# comp-btm.net
KiCad netlist of a schematic drawn in EAGLE
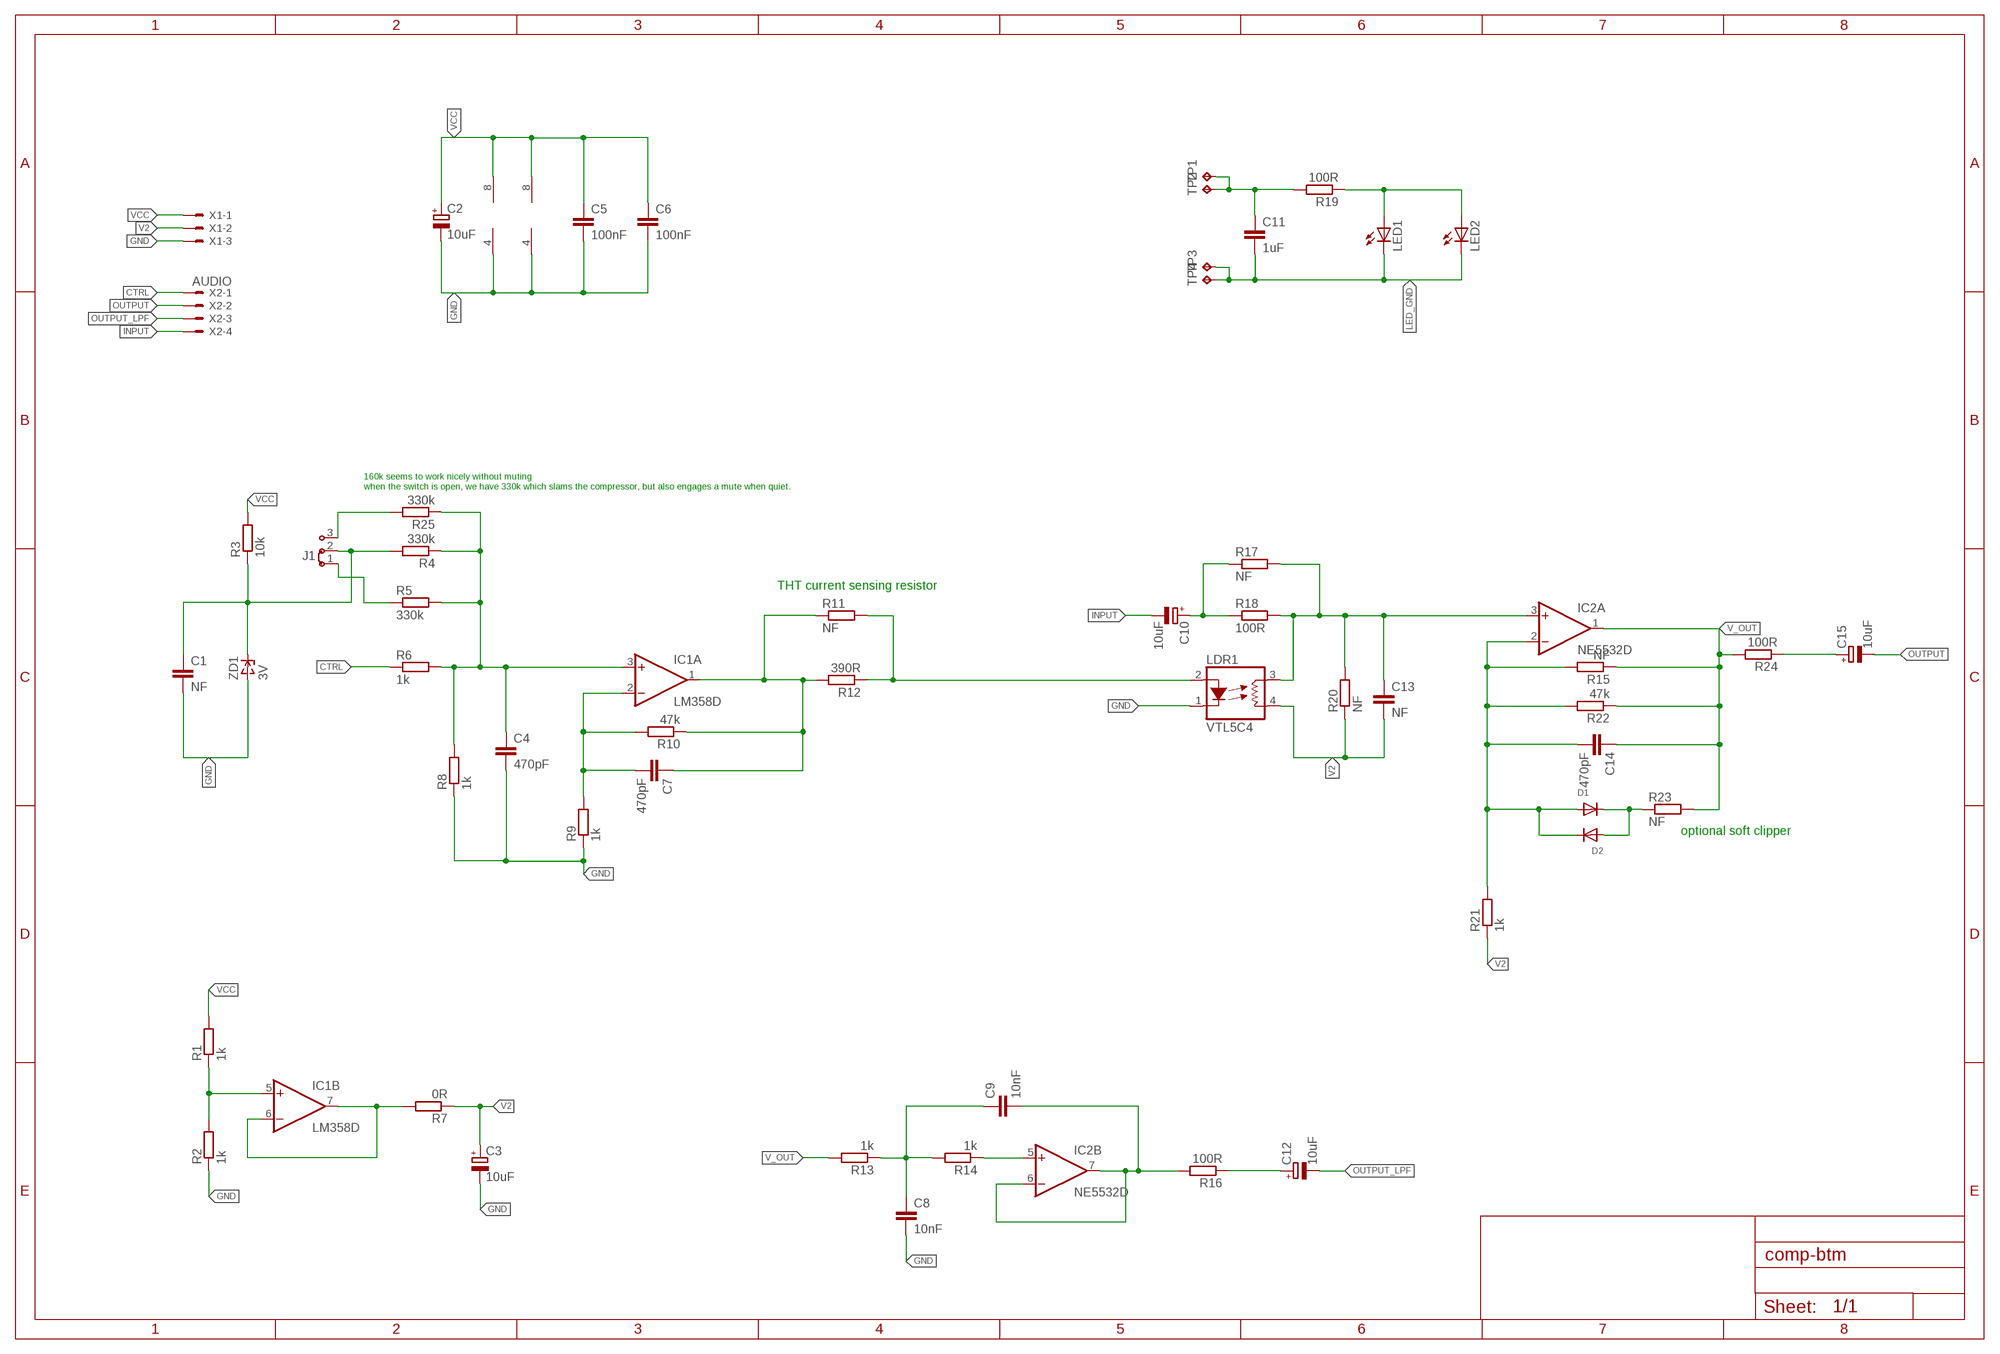
[diagram p0: schematic, sheet 1]

(export (version "E")
  (design (tool "Eeschema 10.0.6"))
  (components
    (comp (ref "C1")
      (value "NF")
      (footprint "eagle-import:C0805")
      (libsource (lib "eagle-import") (part "C-EUC0805"))
    )
    (comp (ref "C2")
      (value "10uF")
      (footprint "eagle-import:E2,5-6E")
      (libsource (lib "eagle-import") (part "CPOL-EUE2,5-6E"))
    )
    (comp (ref "C3")
      (value "10uF")
      (footprint "eagle-import:E2,5-6E")
      (libsource (lib "eagle-import") (part "CPOL-EUE2,5-6E"))
    )
    (comp (ref "C4")
      (value "470pF")
      (footprint "eagle-import:C0805")
      (libsource (lib "eagle-import") (part "C-EUC0805"))
    )
    (comp (ref "C5")
      (value "100nF")
      (footprint "eagle-import:C0805")
      (libsource (lib "eagle-import") (part "C-EUC0805"))
    )
    (comp (ref "C6")
      (value "100nF")
      (footprint "eagle-import:C0805")
      (libsource (lib "eagle-import") (part "C-EUC0805"))
    )
    (comp (ref "C7")
      (value "470pF")
      (footprint "eagle-import:C0805")
      (libsource (lib "eagle-import") (part "C-EUC0805"))
    )
    (comp (ref "C8")
      (value "10nF")
      (footprint "eagle-import:C0805")
      (libsource (lib "eagle-import") (part "C-EUC0805"))
    )
    (comp (ref "C9")
      (value "10nF")
      (footprint "eagle-import:C0805")
      (libsource (lib "eagle-import") (part "C-EUC0805"))
    )
    (comp (ref "C10")
      (value "10uF")
      (footprint "eagle-import:E2,5-6E")
      (libsource (lib "eagle-import") (part "CPOL-EUE2,5-6E"))
    )
    (comp (ref "C11")
      (value "1uF")
      (footprint "eagle-import:C0805")
      (libsource (lib "eagle-import") (part "C-EUC0805"))
    )
    (comp (ref "C12")
      (value "10uF")
      (footprint "eagle-import:E2,5-6E")
      (libsource (lib "eagle-import") (part "CPOL-EUE2,5-6E"))
    )
    (comp (ref "C13")
      (value "NF")
      (footprint "eagle-import:C0805")
      (libsource (lib "eagle-import") (part "C-EUC0805"))
    )
    (comp (ref "C14")
      (value "470pF")
      (footprint "eagle-import:C0805")
      (libsource (lib "eagle-import") (part "C-EUC0805"))
    )
    (comp (ref "C15")
      (value "10uF")
      (footprint "eagle-import:E2,5-6E")
      (libsource (lib "eagle-import") (part "CPOL-EUE2,5-6E"))
    )
    (comp (ref "D1")
      (value "DIODEDO-1N4148")
      (footprint "eagle-import:DO-1N4148")
      (libsource (lib "eagle-import") (part "DIODEDO-1N4148"))
    )
    (comp (ref "D2")
      (value "DIODEDO-1N4148")
      (footprint "eagle-import:DO-1N4148")
      (libsource (lib "eagle-import") (part "DIODEDO-1N4148"))
    )
    (comp (ref "IC1")
      (value "LM358D")
      (footprint "eagle-import:SO08")
      (libsource (lib "eagle-import") (part "LM358D"))
    )
    (comp (ref "IC2")
      (value "NE5532D")
      (footprint "eagle-import:SO08")
      (libsource (lib "eagle-import") (part "NE5532D"))
    )
    (comp (ref "J1")
      (value "J2X2MM")
      (footprint "eagle-import:04C")
      (libsource (lib "eagle-import") (part "J2X2MM"))
    )
    (comp (ref "LDR1")
      (value "VTL5C4")
      (footprint "eagle-import:VTL5C")
      (fields (field (name "MF") "VACTEC PHOTO") (field (name "MPN") "VTL5C9"))
      (libsource (lib "eagle-import") (part "VTL5C9"))
    )
    (comp (ref "LED1")
      (value "LEDCHIPLED_1206")
      (footprint "eagle-import:CHIPLED_1206")
      (libsource (lib "eagle-import") (part "LEDCHIPLED_1206"))
    )
    (comp (ref "LED2")
      (value "LEDCHIPLED_1206")
      (footprint "eagle-import:CHIPLED_1206")
      (libsource (lib "eagle-import") (part "LEDCHIPLED_1206"))
    )
    (comp (ref "R1")
      (value "1k")
      (footprint "eagle-import:R0805")
      (libsource (lib "eagle-import") (part "R-EU_R0805"))
    )
    (comp (ref "R2")
      (value "1k")
      (footprint "eagle-import:R0805")
      (libsource (lib "eagle-import") (part "R-EU_R0805"))
    )
    (comp (ref "R3")
      (value "10k")
      (footprint "eagle-import:R0805")
      (libsource (lib "eagle-import") (part "R-EU_R0805"))
    )
    (comp (ref "R4")
      (value "330k")
      (footprint "eagle-import:R0805")
      (libsource (lib "eagle-import") (part "R-EU_R0805"))
    )
    (comp (ref "R5")
      (value "330k")
      (footprint "eagle-import:R0805")
      (libsource (lib "eagle-import") (part "R-EU_R0805"))
    )
    (comp (ref "R6")
      (value "1k")
      (footprint "eagle-import:R0805")
      (libsource (lib "eagle-import") (part "R-EU_R0805"))
    )
    (comp (ref "R7")
      (value "0R")
      (footprint "eagle-import:R0805")
      (libsource (lib "eagle-import") (part "R-EU_R0805"))
    )
    (comp (ref "R8")
      (value "1k")
      (footprint "eagle-import:R0805")
      (libsource (lib "eagle-import") (part "R-EU_R0805"))
    )
    (comp (ref "R9")
      (value "1k")
      (footprint "eagle-import:R0805")
      (libsource (lib "eagle-import") (part "R-EU_R0805"))
    )
    (comp (ref "R10")
      (value "47k")
      (footprint "eagle-import:R0805")
      (libsource (lib "eagle-import") (part "R-EU_R0805"))
    )
    (comp (ref "R11")
      (value "NF")
      (footprint "eagle-import:0309V")
      (libsource (lib "eagle-import") (part "R-EU_0309/V"))
    )
    (comp (ref "R12")
      (value "390R")
      (footprint "eagle-import:R0805")
      (libsource (lib "eagle-import") (part "R-EU_R0805"))
    )
    (comp (ref "R13")
      (value "1k")
      (footprint "eagle-import:R0805")
      (libsource (lib "eagle-import") (part "R-EU_R0805"))
    )
    (comp (ref "R14")
      (value "1k")
      (footprint "eagle-import:R0805")
      (libsource (lib "eagle-import") (part "R-EU_R0805"))
    )
    (comp (ref "R15")
      (value "NF")
      (footprint "eagle-import:0309V")
      (libsource (lib "eagle-import") (part "R-EU_0309/V"))
    )
    (comp (ref "R16")
      (value "100R")
      (footprint "eagle-import:R0805")
      (libsource (lib "eagle-import") (part "R-EU_R0805"))
    )
    (comp (ref "R17")
      (value "NF")
      (footprint "eagle-import:0309V")
      (libsource (lib "eagle-import") (part "R-EU_0309/V"))
    )
    (comp (ref "R18")
      (value "100R")
      (footprint "eagle-import:R0805")
      (libsource (lib "eagle-import") (part "R-EU_R0805"))
    )
    (comp (ref "R19")
      (value "100R")
      (footprint "eagle-import:R0805")
      (libsource (lib "eagle-import") (part "R-EU_R0805"))
    )
    (comp (ref "R20")
      (value "NF")
      (footprint "eagle-import:R0805")
      (libsource (lib "eagle-import") (part "R-EU_R0805"))
    )
    (comp (ref "R21")
      (value "1k")
      (footprint "eagle-import:R0805")
      (libsource (lib "eagle-import") (part "R-EU_R0805"))
    )
    (comp (ref "R22")
      (value "47k")
      (footprint "eagle-import:R0805")
      (libsource (lib "eagle-import") (part "R-EU_R0805"))
    )
    (comp (ref "R23")
      (value "NF")
      (footprint "eagle-import:0309V")
      (libsource (lib "eagle-import") (part "R-EU_0309/V"))
    )
    (comp (ref "R24")
      (value "100R")
      (footprint "eagle-import:R0805")
      (libsource (lib "eagle-import") (part "R-EU_R0805"))
    )
    (comp (ref "R25")
      (value "330k")
      (footprint "eagle-import:R0805")
      (libsource (lib "eagle-import") (part "R-EU_R0805"))
    )
    (comp (ref "TP1")
      (value "+")
      (footprint "eagle-import:TP20SQ")
      (libsource (lib "eagle-import") (part "TPTP20SQ"))
    )
    (comp (ref "TP2")
      (value "TPTP20SQ")
      (footprint "eagle-import:TP20SQ")
      (libsource (lib "eagle-import") (part "TPTP20SQ"))
    )
    (comp (ref "TP3")
      (value "TPTP20SQ")
      (footprint "eagle-import:TP20SQ")
      (libsource (lib "eagle-import") (part "TPTP20SQ"))
    )
    (comp (ref "TP4")
      (value "TPTP20SQ")
      (footprint "eagle-import:TP20SQ")
      (libsource (lib "eagle-import") (part "TPTP20SQ"))
    )
    (comp (ref "X1")
      (value "POWER")
      (footprint "eagle-import:JST-XH-03-PACKAGE-LONG-PAD")
      (libsource (lib "eagle-import") (part "JST-XH-03-PIN-LONG-PAD"))
    )
    (comp (ref "X2")
      (value "AUDIO")
      (footprint "eagle-import:JST-XH-04-PACKAGE-LONG-PAD")
      (libsource (lib "eagle-import") (part "JST-XH-04-PIN-LONG-PAD"))
    )
    (comp (ref "ZD1")
      (value "3V")
      (footprint "eagle-import:SOD-123")
      (libsource (lib "eagle-import") (part "ZENERSOD-123"))
    )
  )
  (nets
    (net (code "1") (name "CTRL") (class "Default")
      (node (ref "R6") (pin "1") (pinfunction "1_1") (pintype "passive"))
      (node (ref "X2") (pin "1") (pinfunction "S_1") (pintype "passive"))
    )
    (net (code "2") (name "GND") (class "Default")
      (node (ref "C1") (pin "2") (pinfunction "2_2") (pintype "passive"))
      (node (ref "C2") (pin "-") (pinfunction "-_-") (pintype "passive"))
      (node (ref "C3") (pin "-") (pinfunction "-_-") (pintype "passive"))
      (node (ref "C4") (pin "2") (pinfunction "2_2") (pintype "passive"))
      (node (ref "C5") (pin "2") (pinfunction "2_2") (pintype "passive"))
      (node (ref "C6") (pin "2") (pinfunction "2_2") (pintype "passive"))
      (node (ref "C8") (pin "2") (pinfunction "2_2") (pintype "passive"))
      (node (ref "IC1") (pin "4") (pinfunction "V-_4") (pintype "power_in"))
      (node (ref "IC2") (pin "4") (pinfunction "V-_4") (pintype "power_in"))
      (node (ref "LDR1") (pin "1") (pinfunction "C_1") (pintype "passive"))
      (node (ref "R2") (pin "1") (pinfunction "1_1") (pintype "passive"))
      (node (ref "R8") (pin "1") (pinfunction "1_1") (pintype "passive"))
      (node (ref "R9") (pin "1") (pinfunction "1_1") (pintype "passive"))
      (node (ref "X1") (pin "3") (pinfunction "S_3") (pintype "passive"))
      (node (ref "ZD1") (pin "A") (pinfunction "A_A") (pintype "passive"))
    )
    (net (code "3") (name "INPUT") (class "Default")
      (node (ref "C10") (pin "-") (pinfunction "-_-") (pintype "passive"))
      (node (ref "X2") (pin "4") (pinfunction "S_4") (pintype "passive"))
    )
    (net (code "4") (name "LED_GND") (class "Default")
      (node (ref "C11") (pin "2") (pinfunction "2_2") (pintype "passive"))
      (node (ref "LED1") (pin "C") (pinfunction "C_C") (pintype "passive"))
      (node (ref "LED2") (pin "C") (pinfunction "C_C") (pintype "passive"))
      (node (ref "TP3") (pin "TP") (pinfunction "TP_TP") (pintype "input"))
      (node (ref "TP4") (pin "TP") (pinfunction "TP_TP") (pintype "input"))
    )
    (net (code "5") (name "Net-(C1-Pad1)") (class "Default")
      (node (ref "C1") (pin "1") (pinfunction "1_1") (pintype "passive"))
      (node (ref "J1") (pin "2") (pinfunction "2_2") (pintype "passive"))
      (node (ref "R3") (pin "1") (pinfunction "1_1") (pintype "passive"))
      (node (ref "R4") (pin "2") (pinfunction "2_2") (pintype "passive"))
      (node (ref "ZD1") (pin "C") (pinfunction "C_C") (pintype "passive"))
    )
    (net (code "6") (name "Net-(C8-Pad1)") (class "Default")
      (node (ref "C8") (pin "1") (pinfunction "1_1") (pintype "passive"))
      (node (ref "C9") (pin "1") (pinfunction "1_1") (pintype "passive"))
      (node (ref "R13") (pin "1") (pinfunction "1_1") (pintype "passive"))
      (node (ref "R14") (pin "2") (pinfunction "2_2") (pintype "passive"))
    )
    (net (code "7") (name "Net-(C10-Pad+)") (class "Default")
      (node (ref "C10") (pin "+") (pinfunction "+_+") (pintype "passive"))
      (node (ref "R17") (pin "1") (pinfunction "1_1") (pintype "passive"))
      (node (ref "R18") (pin "1") (pinfunction "1_1") (pintype "passive"))
    )
    (net (code "8") (name "Net-(C11-Pad1)") (class "Default")
      (node (ref "C11") (pin "1") (pinfunction "1_1") (pintype "passive"))
      (node (ref "R19") (pin "2") (pinfunction "2_2") (pintype "passive"))
      (node (ref "TP1") (pin "TP") (pinfunction "TP_TP") (pintype "input"))
      (node (ref "TP2") (pin "TP") (pinfunction "TP_TP") (pintype "input"))
    )
    (net (code "9") (name "Net-(C12-Pad+)") (class "Default")
      (node (ref "C12") (pin "+") (pinfunction "+_+") (pintype "passive"))
      (node (ref "R16") (pin "1") (pinfunction "1_1") (pintype "passive"))
    )
    (net (code "10") (name "Net-(C15-Pad+)") (class "Default")
      (node (ref "C15") (pin "+") (pinfunction "+_+") (pintype "passive"))
      (node (ref "R24") (pin "1") (pinfunction "1_1") (pintype "passive"))
    )
    (net (code "11") (name "Net-(D1-PadC)") (class "Default")
      (node (ref "D1") (pin "C") (pinfunction "C_C") (pintype "passive"))
      (node (ref "D2") (pin "A") (pinfunction "A_A") (pintype "passive"))
      (node (ref "R23") (pin "1") (pinfunction "1_1") (pintype "passive"))
    )
    (net (code "12") (name "Net-(IC1A-+IN)") (class "Default")
      (node (ref "C4") (pin "1") (pinfunction "1_1") (pintype "passive"))
      (node (ref "IC1") (pin "3") (pinfunction "+IN_3") (pintype "input"))
      (node (ref "R25") (pin "1") (pinfunction "1_1") (pintype "passive"))
      (node (ref "R4") (pin "1") (pinfunction "1_1") (pintype "passive"))
      (node (ref "R5") (pin "2") (pinfunction "2_2") (pintype "passive"))
      (node (ref "R6") (pin "2") (pinfunction "2_2") (pintype "passive"))
      (node (ref "R8") (pin "2") (pinfunction "2_2") (pintype "passive"))
    )
    (net (code "13") (name "Net-(IC1A--IN)") (class "Default")
      (node (ref "C7") (pin "2") (pinfunction "2_2") (pintype "passive"))
      (node (ref "IC1") (pin "2") (pinfunction "-IN_2") (pintype "input"))
      (node (ref "R10") (pin "2") (pinfunction "2_2") (pintype "passive"))
      (node (ref "R9") (pin "2") (pinfunction "2_2") (pintype "passive"))
    )
    (net (code "14") (name "Net-(IC1A-OUT)") (class "Default")
      (node (ref "C7") (pin "1") (pinfunction "1_1") (pintype "passive"))
      (node (ref "IC1") (pin "1") (pinfunction "OUT_1") (pintype "output"))
      (node (ref "R10") (pin "1") (pinfunction "1_1") (pintype "passive"))
      (node (ref "R11") (pin "1") (pinfunction "1_1") (pintype "passive"))
      (node (ref "R12") (pin "2") (pinfunction "2_2") (pintype "passive"))
    )
    (net (code "15") (name "Net-(IC1B-+IN)") (class "Default")
      (node (ref "IC1") (pin "5") (pinfunction "+IN_5") (pintype "input"))
      (node (ref "R1") (pin "1") (pinfunction "1_1") (pintype "passive"))
      (node (ref "R2") (pin "2") (pinfunction "2_2") (pintype "passive"))
    )
    (net (code "16") (name "Net-(IC1B--IN)") (class "Default")
      (node (ref "IC1") (pin "6") (pinfunction "-IN_6") (pintype "input"))
      (node (ref "IC1") (pin "7") (pinfunction "OUT_7") (pintype "output"))
      (node (ref "R7") (pin "2") (pinfunction "2_2") (pintype "passive"))
    )
    (net (code "17") (name "Net-(IC2A-+IN)") (class "Default")
      (node (ref "C13") (pin "1") (pinfunction "1_1") (pintype "passive"))
      (node (ref "IC2") (pin "3") (pinfunction "+IN_3") (pintype "input"))
      (node (ref "LDR1") (pin "3") (pinfunction "L1_3") (pintype "passive"))
      (node (ref "R17") (pin "2") (pinfunction "2_2") (pintype "passive"))
      (node (ref "R18") (pin "2") (pinfunction "2_2") (pintype "passive"))
      (node (ref "R20") (pin "2") (pinfunction "2_2") (pintype "passive"))
    )
    (net (code "18") (name "Net-(IC2A--IN)") (class "Default")
      (node (ref "C14") (pin "2") (pinfunction "2_2") (pintype "passive"))
      (node (ref "D1") (pin "A") (pinfunction "A_A") (pintype "passive"))
      (node (ref "D2") (pin "C") (pinfunction "C_C") (pintype "passive"))
      (node (ref "IC2") (pin "2") (pinfunction "-IN_2") (pintype "input"))
      (node (ref "R15") (pin "2") (pinfunction "2_2") (pintype "passive"))
      (node (ref "R21") (pin "2") (pinfunction "2_2") (pintype "passive"))
      (node (ref "R22") (pin "2") (pinfunction "2_2") (pintype "passive"))
    )
    (net (code "19") (name "Net-(IC2B-+IN)") (class "Default")
      (node (ref "IC2") (pin "5") (pinfunction "+IN_5") (pintype "input"))
      (node (ref "R14") (pin "1") (pinfunction "1_1") (pintype "passive"))
    )
    (net (code "20") (name "Net-(IC2B--IN)") (class "Default")
      (node (ref "C9") (pin "2") (pinfunction "2_2") (pintype "passive"))
      (node (ref "IC2") (pin "6") (pinfunction "-IN_6") (pintype "input"))
      (node (ref "IC2") (pin "7") (pinfunction "OUT_7") (pintype "output"))
      (node (ref "R16") (pin "2") (pinfunction "2_2") (pintype "passive"))
    )
    (net (code "21") (name "Net-(J1-Pad1)") (class "Default")
      (node (ref "J1") (pin "1") (pinfunction "1_1") (pintype "passive"))
      (node (ref "R5") (pin "1") (pinfunction "1_1") (pintype "passive"))
    )
    (net (code "22") (name "Net-(J1-Pad3)") (class "Default")
      (node (ref "J1") (pin "3") (pinfunction "3_3") (pintype "passive"))
      (node (ref "R25") (pin "2") (pinfunction "2_2") (pintype "passive"))
    )
    (net (code "23") (name "Net-(LDR1-A)") (class "Default")
      (node (ref "LDR1") (pin "2") (pinfunction "A_2") (pintype "passive"))
      (node (ref "R11") (pin "2") (pinfunction "2_2") (pintype "passive"))
      (node (ref "R12") (pin "1") (pinfunction "1_1") (pintype "passive"))
    )
    (net (code "24") (name "Net-(LED1-PadA)") (class "Default")
      (node (ref "LED1") (pin "A") (pinfunction "A_A") (pintype "passive"))
      (node (ref "LED2") (pin "A") (pinfunction "A_A") (pintype "passive"))
      (node (ref "R19") (pin "1") (pinfunction "1_1") (pintype "passive"))
    )
    (net (code "25") (name "OUTPUT") (class "Default")
      (node (ref "C15") (pin "-") (pinfunction "-_-") (pintype "passive"))
      (node (ref "X2") (pin "2") (pinfunction "S_2") (pintype "passive"))
    )
    (net (code "26") (name "OUTPUT_LPF") (class "Default")
      (node (ref "C12") (pin "-") (pinfunction "-_-") (pintype "passive"))
      (node (ref "X2") (pin "3") (pinfunction "S_3") (pintype "passive"))
    )
    (net (code "27") (name "V2") (class "Default")
      (node (ref "C13") (pin "2") (pinfunction "2_2") (pintype "passive"))
      (node (ref "C3") (pin "+") (pinfunction "+_+") (pintype "passive"))
      (node (ref "LDR1") (pin "4") (pinfunction "L2_4") (pintype "passive"))
      (node (ref "R20") (pin "1") (pinfunction "1_1") (pintype "passive"))
      (node (ref "R21") (pin "1") (pinfunction "1_1") (pintype "passive"))
      (node (ref "R7") (pin "1") (pinfunction "1_1") (pintype "passive"))
      (node (ref "X1") (pin "2") (pinfunction "S_2") (pintype "passive"))
    )
    (net (code "28") (name "VCC") (class "Default")
      (node (ref "C2") (pin "+") (pinfunction "+_+") (pintype "passive"))
      (node (ref "C5") (pin "1") (pinfunction "1_1") (pintype "passive"))
      (node (ref "C6") (pin "1") (pinfunction "1_1") (pintype "passive"))
      (node (ref "IC1") (pin "8") (pinfunction "V+_8") (pintype "power_in"))
      (node (ref "IC2") (pin "8") (pinfunction "V+_8") (pintype "power_in"))
      (node (ref "R1") (pin "2") (pinfunction "2_2") (pintype "passive"))
      (node (ref "R3") (pin "2") (pinfunction "2_2") (pintype "passive"))
      (node (ref "X1") (pin "1") (pinfunction "S_1") (pintype "passive"))
    )
    (net (code "29") (name "V_OUT") (class "Default")
      (node (ref "C14") (pin "1") (pinfunction "1_1") (pintype "passive"))
      (node (ref "IC2") (pin "1") (pinfunction "OUT_1") (pintype "output"))
      (node (ref "R13") (pin "2") (pinfunction "2_2") (pintype "passive"))
      (node (ref "R15") (pin "1") (pinfunction "1_1") (pintype "passive"))
      (node (ref "R22") (pin "1") (pinfunction "1_1") (pintype "passive"))
      (node (ref "R23") (pin "2") (pinfunction "2_2") (pintype "passive"))
      (node (ref "R24") (pin "2") (pinfunction "2_2") (pintype "passive"))
    )
  )
)
